# ST-LINK_V2-1_Klinovitskiy_Kirill.net
KiCad netlist of a schematic drawn in Altium Designer
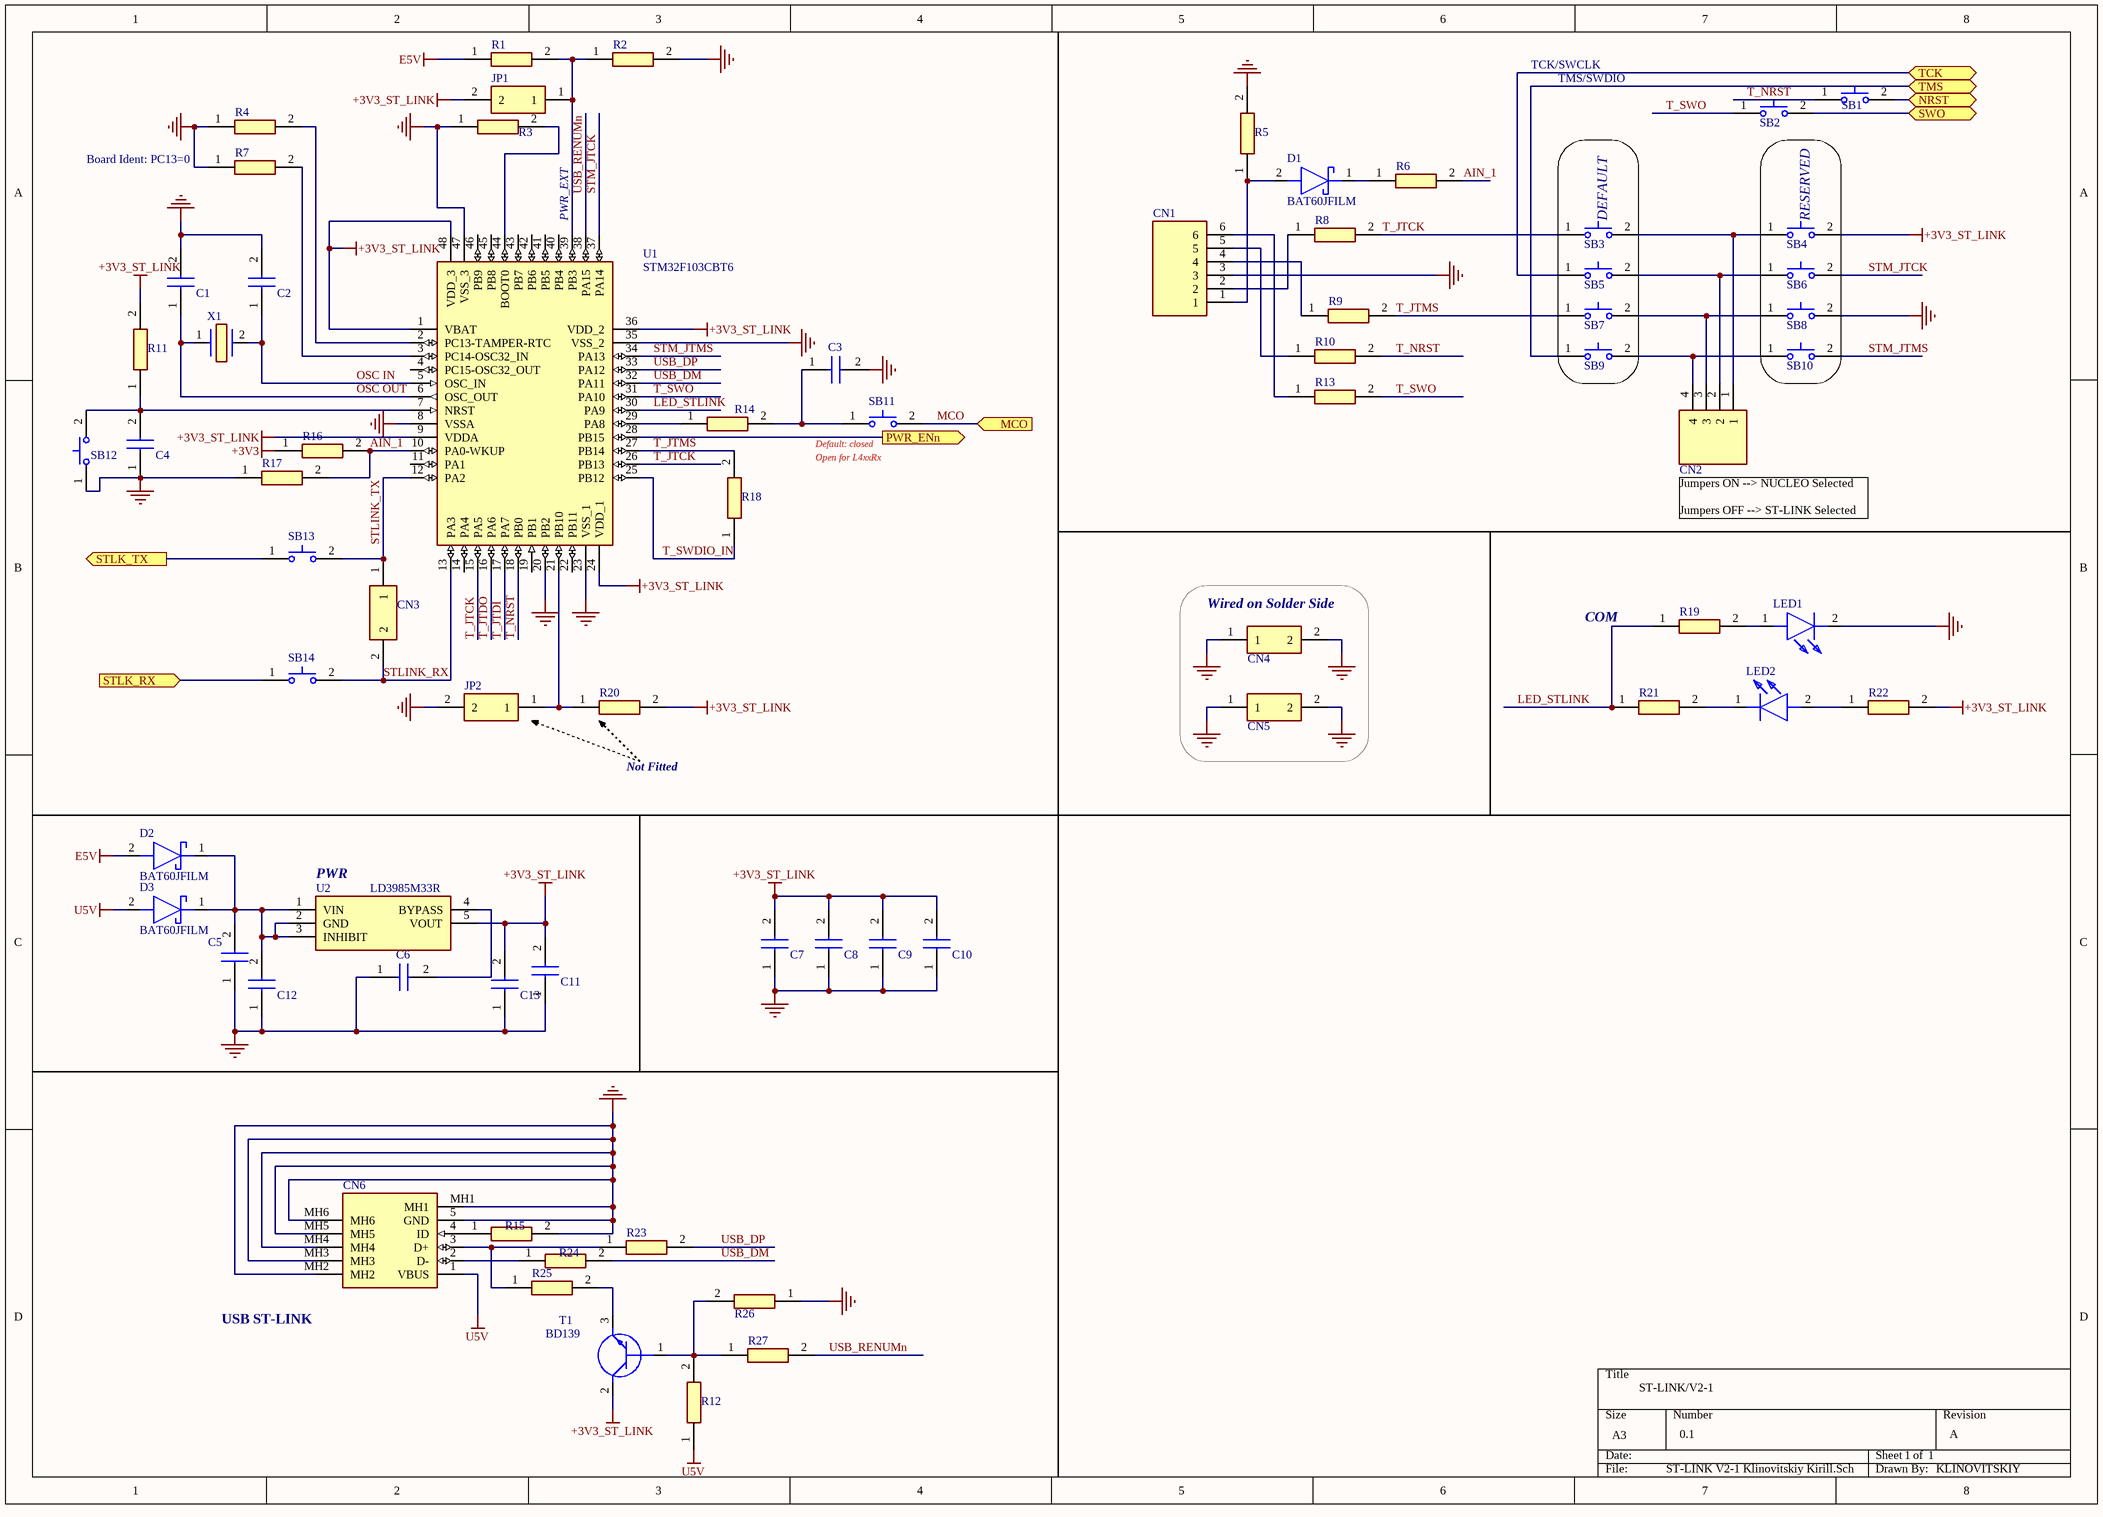
[diagram p0: ST-LINK V2-1 Klinovitskiy Kirill.SchDoc]

(export (version "E")
  (design (tool "Eeschema 10.0.6"))
  (components
    (comp (ref "C1")
      (value "C1206C200KCGACTU")
      (footprint "SamacSys:C1206")
      (description "Capacitor")
      (libsource (lib "*") (part "C1206C200KCGACTU"))
    )
    (comp (ref "C2")
      (value "C1206C200KCGACTU")
      (footprint "SamacSys:C1206")
      (description "Capacitor")
      (libsource (lib "*") (part "C1206C200KCGACTU"))
    )
    (comp (ref "C3")
      (value "C1206C200KCGACTU")
      (footprint "SamacSys:C1206")
      (description "Capacitor")
      (libsource (lib "*") (part "C1206C200KCGACTU"))
    )
    (comp (ref "C4")
      (value "06035C104K4T4A")
      (footprint "SamacSys:CAPC1608X90N")
      (description "Capacitor")
      (fields (field (name "MOUSER PART NUMBER") "581-06035C104K4T4A"))
      (libsource (lib "*") (part "06035C104K4T4A"))
    )
    (comp (ref "C5")
      (value "MAJCT168BB7105KTEA01")
      (footprint "SamacSys:MAJx16")
      (description "Capacitor")
      (libsource (lib "*") (part "MAJCT168BB7105KTEA01"))
    )
    (comp (ref "C6")
      (value "KGM31GCG2J103JU")
      (footprint "SamacSys:CAPC3316X145N")
      (description "Capacitor")
      (fields (field (name "MOUSER PART NUMBER") "581-KGM31GCG2J103JU"))
      (libsource (lib "*") (part "KGM31GCG2J103JU"))
    )
    (comp (ref "C7")
      (value "06035C104K4T4A")
      (footprint "SamacSys:CAPC1608X90N")
      (description "Capacitor")
      (fields (field (name "MOUSER PART NUMBER") "581-06035C104K4T4A"))
      (libsource (lib "*") (part "06035C104K4T4A"))
    )
    (comp (ref "C8")
      (value "06035C104K4T4A")
      (footprint "SamacSys:CAPC1608X90N")
      (description "Capacitor")
      (fields (field (name "MOUSER PART NUMBER") "581-06035C104K4T4A"))
      (libsource (lib "*") (part "06035C104K4T4A"))
    )
    (comp (ref "C9")
      (value "06035C104K4T4A")
      (footprint "SamacSys:CAPC1608X90N")
      (description "Capacitor")
      (fields (field (name "MOUSER PART NUMBER") "581-06035C104K4T4A"))
      (libsource (lib "*") (part "06035C104K4T4A"))
    )
    (comp (ref "C10")
      (value "06035C104K4T4A")
      (footprint "SamacSys:CAPC1608X90N")
      (description "Capacitor")
      (fields (field (name "MOUSER PART NUMBER") "581-06035C104K4T4A"))
      (libsource (lib "*") (part "06035C104K4T4A"))
    )
    (comp (ref "C11")
      (value "06035C104K4T4A")
      (footprint "SamacSys:CAPC1608X90N")
      (description "Capacitor")
      (fields (field (name "MOUSER PART NUMBER") "581-06035C104K4T4A"))
      (libsource (lib "*") (part "06035C104K4T4A"))
    )
    (comp (ref "C12")
      (value "06035C104K4T4A")
      (footprint "SamacSys:CAPC1608X90N")
      (description "Capacitor")
      (fields (field (name "MOUSER PART NUMBER") "581-06035C104K4T4A"))
      (libsource (lib "*") (part "06035C104K4T4A"))
    )
    (comp (ref "C13")
      (value "MAJCT168BB7105KTEA01")
      (footprint "SamacSys:MAJx16")
      (description "Capacitor")
      (libsource (lib "*") (part "MAJCT168BB7105KTEA01"))
    )
    (comp (ref "CN1")
      (value "22-28-4062")
      (footprint "SamacSys:HDRV6W66P0X254_1X6_1524X249X838P")
      (description "Connector")
      (fields (field (name "MOUSER PART NUMBER") "538-22-28-4062"))
      (libsource (lib "*") (part "22-28-4062"))
    )
    (comp (ref "CN2")
      (value "53014-0410")
      (footprint "SamacSys:SHDR4W60P0X200_1X4_1200X435X1000P")
      (description "Connector")
      (fields (field (name "MOUSER PART NUMBER") "538-53014-0410"))
      (libsource (lib "*") (part "53014-0410"))
    )
    (comp (ref "CN3")
      (value "3-647166-2")
      (footprint "SamacSys:36471662")
      (description "Connector")
      (fields (field (name "MOUSER PART NUMBER") "571-3-647166-2"))
      (libsource (lib "") (part "3-647166-2_2"))
    )
    (comp (ref "CN4")
      (value "3-647166-2")
      (footprint "SamacSys:36471662")
      (description "Connector")
      (fields (field (name "MOUSER PART NUMBER") "571-3-647166-2"))
      (libsource (lib "*") (part "3-647166-2"))
    )
    (comp (ref "CN5")
      (value "3-647166-2")
      (footprint "SamacSys:36471662")
      (description "Connector")
      (fields (field (name "MOUSER PART NUMBER") "571-3-647166-2"))
      (libsource (lib "*") (part "3-647166-2"))
    )
    (comp (ref "CN6")
      (value "204926-1103")
      (footprint "SamacSys:2049261103")
      (description "Connector")
      (fields (field (name "MOUSER PART NUMBER") "538-204926-1103"))
      (libsource (lib "*") (part "204926-1103"))
    )
    (comp (ref "D1")
      (value "BAT60JFILM")
      (footprint "SamacSys:SOD2513X117N")
      (description "Schottky Diode")
      (fields (field (name "MOUSER PART NUMBER") "511-BAT60JFILM"))
      (libsource (lib "*") (part "BAT60JFILM"))
    )
    (comp (ref "D2")
      (value "BAT60JFILM")
      (footprint "SamacSys:SOD2513X117N")
      (description "Schottky Diode")
      (fields (field (name "MOUSER PART NUMBER") "511-BAT60JFILM"))
      (libsource (lib "*") (part "BAT60JFILM"))
    )
    (comp (ref "D3")
      (value "BAT60JFILM")
      (footprint "SamacSys:SOD2513X117N")
      (description "Schottky Diode")
      (fields (field (name "MOUSER PART NUMBER") "511-BAT60JFILM"))
      (libsource (lib "*") (part "BAT60JFILM"))
    )
    (comp (ref "JP1")
      (value "3-647166-2")
      (footprint "SamacSys:36471662")
      (description "Connector")
      (fields (field (name "MOUSER PART NUMBER") "571-3-647166-2"))
      (libsource (lib "") (part "3-647166-2_1"))
    )
    (comp (ref "JP2")
      (value "3-647166-2")
      (footprint "SamacSys:36471662")
      (description "Connector")
      (fields (field (name "MOUSER PART NUMBER") "571-3-647166-2"))
      (libsource (lib "") (part "3-647166-2_1"))
    )
    (comp (ref "LED1")
      (value "C4SMA-RGY-CS4V1BB1")
      (footprint "SamacSys:C4SMARGYCS4V1BB1")
      (description "LED")
      (fields (field (name "MOUSER PART NUMBER") "941-C4SMARGYCS4V1BB1"))
      (libsource (lib "*") (part "C4SMA-RGY-CS4V1BB1"))
    )
    (comp (ref "LED2")
      (value "TLHG5420-ASZ")
      (footprint "SamacSys:TLHG5420ASZ")
      (description "LED")
      (fields (field (name "MOUSER PART NUMBER") "78-TLHG5420-ASZ"))
      (libsource (lib "*") (part "TLHG5420-ASZ"))
    )
    (comp (ref "R1")
      (value "CRCW12102K70FKEAHP")
      (footprint "SamacSys:RESC3225X70N")
      (description "Resistor")
      (fields (field (name "MOUSER PART NUMBER") "71-CRCW12102K70FKEAH"))
      (libsource (lib "*") (part "CRCW12102K70FKEAHP"))
    )
    (comp (ref "R2")
      (value "MCS04020D4701BE000")
      (footprint "SamacSys:RESC1005X37N")
      (description "Resistor")
      (fields (field (name "MOUSER PART NUMBER") "594-MCS04020D4701BE0"))
      (libsource (lib "*") (part "MCS04020D4701BE000"))
    )
    (comp (ref "R3")
      (value "SFR01MZPF1003")
      (footprint "SamacSys:RESC1005X40N")
      (description "Resistor")
      (fields (field (name "MOUSER PART NUMBER") "755-SFR01MZPF1003"))
      (libsource (lib "") (part "SFR01MZPF1003_1"))
    )
    (comp (ref "R4")
      (value "CRM2512QJW-103ELF")
      (footprint "SamacSys:RESC6331X80N")
      (description "Resistor")
      (fields (field (name "MOUSER PART NUMBER") "652-CRM2512QJW-103E"))
      (libsource (lib "*") (part "CRM2512QJW-103ELF"))
    )
    (comp (ref "R5")
      (value "CRM2512QJW-103ELF")
      (footprint "SamacSys:RESC6331X80N")
      (description "Resistor")
      (fields (field (name "MOUSER PART NUMBER") "652-CRM2512QJW-103E"))
      (libsource (lib "") (part "CRM2512QJW-103ELF_1"))
    )
    (comp (ref "R6")
      (value "ERA-3AED101V")
      (footprint "SamacSys:ERA3AEB101V")
      (description "Resistor")
      (fields (field (name "MOUSER PART NUMBER") "667-ERA-3AED101V"))
      (libsource (lib "*") (part "ERA-3AED101V"))
    )
    (comp (ref "R7")
      (value "CRM2512QJW-103ELF")
      (footprint "SamacSys:RESC6331X80N")
      (description "Resistor")
      (fields (field (name "MOUSER PART NUMBER") "652-CRM2512QJW-103E"))
      (libsource (lib "*") (part "CRM2512QJW-103ELF"))
    )
    (comp (ref "R8")
      (value "ERA-6AHD220V")
      (footprint "SamacSys:ERA6AEB1020V")
      (description "Resistor")
      (fields (field (name "MOUSER PART NUMBER") "667-ERA-6AHD220V"))
      (libsource (lib "*") (part "ERA-6AHD220V"))
    )
    (comp (ref "R9")
      (value "ERA-6AHD220V")
      (footprint "SamacSys:ERA6AEB1020V")
      (description "Resistor")
      (fields (field (name "MOUSER PART NUMBER") "667-ERA-6AHD220V"))
      (libsource (lib "*") (part "ERA-6AHD220V"))
    )
    (comp (ref "R10")
      (value "ERA-6AHD220V")
      (footprint "SamacSys:ERA6AEB1020V")
      (description "Resistor")
      (fields (field (name "MOUSER PART NUMBER") "667-ERA-6AHD220V"))
      (libsource (lib "*") (part "ERA-6AHD220V"))
    )
    (comp (ref "R11")
      (value "SFR01MZPF1003")
      (footprint "SamacSys:RESC1005X40N")
      (description "Resistor")
      (fields (field (name "MOUSER PART NUMBER") "755-SFR01MZPF1003"))
      (libsource (lib "*") (part "SFR01MZPF1003"))
    )
    (comp (ref "R12")
      (value "CRM2512QJW-103ELF")
      (footprint "SamacSys:RESC6331X80N")
      (description "Resistor")
      (fields (field (name "MOUSER PART NUMBER") "652-CRM2512QJW-103E"))
      (libsource (lib "") (part "CRM2512QJW-103ELF_1"))
    )
    (comp (ref "R13")
      (value "ERA-6AHD220V")
      (footprint "SamacSys:ERA6AEB1020V")
      (description "Resistor")
      (fields (field (name "MOUSER PART NUMBER") "667-ERA-6AHD220V"))
      (libsource (lib "*") (part "ERA-6AHD220V"))
    )
    (comp (ref "R14")
      (value "ERA-3AED101V")
      (footprint "SamacSys:ERA3AEB101V")
      (description "Resistor")
      (fields (field (name "MOUSER PART NUMBER") "667-ERA-3AED101V"))
      (libsource (lib "*") (part "ERA-3AED101V"))
    )
    (comp (ref "R15")
      (value "SFR01MZPF1003")
      (footprint "SamacSys:RESC1005X40N")
      (description "Resistor")
      (fields (field (name "MOUSER PART NUMBER") "755-SFR01MZPF1003"))
      (libsource (lib "") (part "SFR01MZPF1003_1"))
    )
    (comp (ref "R16")
      (value "MCS04020D4701BE000")
      (footprint "SamacSys:RESC1005X37N")
      (description "Resistor")
      (fields (field (name "MOUSER PART NUMBER") "594-MCS04020D4701BE0"))
      (libsource (lib "*") (part "MCS04020D4701BE000"))
    )
    (comp (ref "R17")
      (value "MCS04020D4701BE000")
      (footprint "SamacSys:RESC1005X37N")
      (description "Resistor")
      (fields (field (name "MOUSER PART NUMBER") "594-MCS04020D4701BE0"))
      (libsource (lib "*") (part "MCS04020D4701BE000"))
    )
    (comp (ref "R18")
      (value "ERA-3AED101V")
      (footprint "SamacSys:ERA3AEB101V")
      (description "Resistor")
      (fields (field (name "MOUSER PART NUMBER") "667-ERA-3AED101V"))
      (libsource (lib "") (part "ERA-3AED101V_1"))
    )
    (comp (ref "R19")
      (value "ERA-3AED101V")
      (footprint "SamacSys:ERA3AEB101V")
      (description "Resistor")
      (fields (field (name "MOUSER PART NUMBER") "667-ERA-3AED101V"))
      (libsource (lib "*") (part "ERA-3AED101V"))
    )
    (comp (ref "R20")
      (value "WSL080500000ZEA9")
      (footprint "SamacSys:RESC2013X84N")
      (description "Resistor")
      (fields (field (name "MOUSER PART NUMBER") "71-WSL080500000ZEA9"))
      (libsource (lib "*") (part "WSL080500000ZEA9"))
    )
    (comp (ref "R21")
      (value "ERA-3AED101V")
      (footprint "SamacSys:ERA3AEB101V")
      (description "Resistor")
      (fields (field (name "MOUSER PART NUMBER") "667-ERA-3AED101V"))
      (libsource (lib "*") (part "ERA-3AED101V"))
    )
    (comp (ref "R22")
      (value "WSL080500000ZEA9")
      (footprint "SamacSys:RESC2013X84N")
      (description "Resistor")
      (fields (field (name "MOUSER PART NUMBER") "71-WSL080500000ZEA9"))
      (libsource (lib "*") (part "WSL080500000ZEA9"))
    )
    (comp (ref "R23")
      (value "WSL080500000ZEA9")
      (footprint "SamacSys:RESC2013X84N")
      (description "Resistor")
      (fields (field (name "MOUSER PART NUMBER") "71-WSL080500000ZEA9"))
      (libsource (lib "*") (part "WSL080500000ZEA9"))
    )
    (comp (ref "R24")
      (value "WSL080500000ZEA9")
      (footprint "SamacSys:RESC2013X84N")
      (description "Resistor")
      (fields (field (name "MOUSER PART NUMBER") "71-WSL080500000ZEA9"))
      (libsource (lib "*") (part "WSL080500000ZEA9"))
    )
    (comp (ref "R25")
      (value "CRCW12061K50FKEAHP")
      (footprint "SamacSys:RESC3116X65N")
      (description "Resistor")
      (fields (field (name "MOUSER PART NUMBER") "71-CRCW12061K50FKEAH"))
      (libsource (lib "*") (part "CRCW12061K50FKEAHP"))
    )
    (comp (ref "R26")
      (value "TNPW080536K0BEEA")
      (footprint "SamacSys:RESC2012X55N")
      (description "Resistor")
      (libsource (lib "*") (part "TNPW080536K0BEEA"))
    )
    (comp (ref "R27")
      (value "ERA-3AED101V")
      (footprint "SamacSys:ERA3AEB101V")
      (description "Resistor")
      (fields (field (name "MOUSER PART NUMBER") "667-ERA-3AED101V"))
      (libsource (lib "*") (part "ERA-3AED101V"))
    )
    (comp (ref "SB1")
      (value "8631CQD2")
      (footprint "SamacSys:8631CQD2")
      (description "Switch (2-Pin Push)")
      (fields (field (name "MOUSER PART NUMBER") "611-8631-261"))
      (libsource (lib "*") (part "8631CQD2"))
    )
    (comp (ref "SB2")
      (value "8631CQD2")
      (footprint "SamacSys:8631CQD2")
      (description "Switch (2-Pin Push)")
      (fields (field (name "MOUSER PART NUMBER") "611-8631-261"))
      (libsource (lib "*") (part "8631CQD2"))
    )
    (comp (ref "SB3")
      (value "8631CQD2")
      (footprint "SamacSys:8631CQD2")
      (description "Switch (2-Pin Push)")
      (fields (field (name "MOUSER PART NUMBER") "611-8631-261"))
      (libsource (lib "*") (part "8631CQD2"))
    )
    (comp (ref "SB4")
      (value "8631CQD2")
      (footprint "SamacSys:8631CQD2")
      (description "Switch (2-Pin Push)")
      (fields (field (name "MOUSER PART NUMBER") "611-8631-261"))
      (libsource (lib "*") (part "8631CQD2"))
    )
    (comp (ref "SB5")
      (value "8631CQD2")
      (footprint "SamacSys:8631CQD2")
      (description "Switch (2-Pin Push)")
      (fields (field (name "MOUSER PART NUMBER") "611-8631-261"))
      (libsource (lib "*") (part "8631CQD2"))
    )
    (comp (ref "SB6")
      (value "8631CQD2")
      (footprint "SamacSys:8631CQD2")
      (description "Switch (2-Pin Push)")
      (fields (field (name "MOUSER PART NUMBER") "611-8631-261"))
      (libsource (lib "*") (part "8631CQD2"))
    )
    (comp (ref "SB7")
      (value "8631CQD2")
      (footprint "SamacSys:8631CQD2")
      (description "Switch (2-Pin Push)")
      (fields (field (name "MOUSER PART NUMBER") "611-8631-261"))
      (libsource (lib "*") (part "8631CQD2"))
    )
    (comp (ref "SB8")
      (value "8631CQD2")
      (footprint "SamacSys:8631CQD2")
      (description "Switch (2-Pin Push)")
      (fields (field (name "MOUSER PART NUMBER") "611-8631-261"))
      (libsource (lib "*") (part "8631CQD2"))
    )
    (comp (ref "SB9")
      (value "8631CQD2")
      (footprint "SamacSys:8631CQD2")
      (description "Switch (2-Pin Push)")
      (fields (field (name "MOUSER PART NUMBER") "611-8631-261"))
      (libsource (lib "*") (part "8631CQD2"))
    )
    (comp (ref "SB10")
      (value "8631CQD2")
      (footprint "SamacSys:8631CQD2")
      (description "Switch (2-Pin Push)")
      (fields (field (name "MOUSER PART NUMBER") "611-8631-261"))
      (libsource (lib "*") (part "8631CQD2"))
    )
    (comp (ref "SB11")
      (value "8631CQD2")
      (footprint "SamacSys:8631CQD2")
      (description "Switch (2-Pin Push)")
      (fields (field (name "MOUSER PART NUMBER") "611-8631-261"))
      (libsource (lib "*") (part "8631CQD2"))
    )
    (comp (ref "SB12")
      (value "8631CQD2")
      (footprint "SamacSys:8631CQD2")
      (description "Switch (2-Pin Push)")
      (fields (field (name "MOUSER PART NUMBER") "611-8631-261"))
      (libsource (lib "*") (part "8631CQD2"))
    )
    (comp (ref "SB13")
      (value "8631CQD2")
      (footprint "SamacSys:8631CQD2")
      (description "Switch (2-Pin Push)")
      (fields (field (name "MOUSER PART NUMBER") "611-8631-261"))
      (libsource (lib "*") (part "8631CQD2"))
    )
    (comp (ref "SB14")
      (value "8631CQD2")
      (footprint "SamacSys:8631CQD2")
      (description "Switch (2-Pin Push)")
      (fields (field (name "MOUSER PART NUMBER") "611-8631-261"))
      (libsource (lib "*") (part "8631CQD2"))
    )
    (comp (ref "T1")
      (value "BD139")
      (footprint "SamacSys:TO254P290X760X1320-3P")
      (description "Transistor BJT NPN")
      (fields (field (name "MOUSER PART NUMBER") "511-BD139"))
      (libsource (lib "*") (part "BD139"))
    )
    (comp (ref "U1")
      (value "STM32F103CBT6")
      (footprint "SamacSys:QFP50P900X900X160-48N")
      (description "Integrated Circuit")
      (fields (field (name "MOUSER PART NUMBER") "511-STM32F103CBT6"))
      (libsource (lib "*") (part "STM32F103CBT6"))
    )
    (comp (ref "U2")
      (value "LD3985M33R")
      (footprint "SamacSys:SOT95P280X145-5N")
      (description "Integrated Circuit")
      (fields (field (name "MOUSER PART NUMBER") "511-LD3985M33R"))
      (libsource (lib "*") (part "LD3985M33R"))
    )
    (comp (ref "X1")
      (value "ECS-80-12-5PX-GM-TR")
      (footprint "SamacSys:ECS80125PXGMTR")
      (description "Crystal or Oscillator")
      (fields (field (name "MOUSER PART NUMBER") "520-80-12-5PX-GM-TR"))
      (libsource (lib "*") (part "ECS-80-12-5PX-GM-TR"))
    )
  )
  (nets
    (net (code "1") (name "+3V3") (class "Default")
      (node (ref "R16") (pin "1") (pinfunction "1_1") (pintype "passive"))
    )
    (net (code "2") (name "+3V3_ST_LINK") (class "Default")
      (node (ref "C10") (pin "2") (pinfunction "2_2") (pintype "passive"))
      (node (ref "C11") (pin "2") (pinfunction "2_2") (pintype "passive"))
      (node (ref "C13") (pin "2") (pinfunction "2_2") (pintype "passive"))
      (node (ref "C7") (pin "2") (pinfunction "2_2") (pintype "passive"))
      (node (ref "C8") (pin "2") (pinfunction "2_2") (pintype "passive"))
      (node (ref "C9") (pin "2") (pinfunction "2_2") (pintype "passive"))
      (node (ref "JP1") (pin "2") (pinfunction "2_2") (pintype "passive"))
      (node (ref "R11") (pin "2") (pinfunction "2_2") (pintype "passive"))
      (node (ref "R20") (pin "2") (pinfunction "2_2") (pintype "passive"))
      (node (ref "R22") (pin "2") (pinfunction "2_2") (pintype "passive"))
      (node (ref "SB4") (pin "2") (pinfunction "N.O._2_2") (pintype "passive"))
      (node (ref "T1") (pin "2") (pinfunction "C_2") (pintype "passive"))
      (node (ref "U1") (pin "1") (pinfunction "VBAT_1") (pintype "passive"))
      (node (ref "U1") (pin "24") (pinfunction "VDD_1_24") (pintype "passive"))
      (node (ref "U1") (pin "36") (pinfunction "VDD_2_36") (pintype "passive"))
      (node (ref "U1") (pin "48") (pinfunction "VDD_3_48") (pintype "passive"))
      (node (ref "U1") (pin "9") (pinfunction "VDDA_9") (pintype "passive"))
      (node (ref "U2") (pin "5") (pinfunction "VOUT_5") (pintype "passive"))
    )
    (net (code "3") (name "/AIN_1") (class "Default")
      (node (ref "R16") (pin "2") (pinfunction "2_2") (pintype "passive"))
      (node (ref "R17") (pin "2") (pinfunction "2_2") (pintype "passive"))
      (node (ref "R6") (pin "2") (pinfunction "2_2") (pintype "passive"))
      (node (ref "U1") (pin "10") (pinfunction "PA0-WKUP_10") (pintype "bidirectional"))
    )
    (net (code "4") (name "/LED_STLINK") (class "Default")
      (node (ref "R19") (pin "1") (pinfunction "1_1") (pintype "passive"))
      (node (ref "R21") (pin "1") (pinfunction "1_1") (pintype "passive"))
      (node (ref "U1") (pin "30") (pinfunction "PA9_30") (pintype "bidirectional"))
    )
    (net (code "5") (name "/MCO") (class "Default")
      (node (ref "SB11") (pin "2") (pinfunction "N.O._2_2") (pintype "passive"))
    )
    (net (code "6") (name "/NRST") (class "Default")
      (node (ref "SB1") (pin "2") (pinfunction "N.O._2_2") (pintype "passive"))
    )
    (net (code "7") (name "/OSC IN") (class "Default")
      (node (ref "C2") (pin "1") (pinfunction "1_1") (pintype "passive"))
      (node (ref "U1") (pin "5") (pinfunction "OSC_IN_5") (pintype "input"))
      (node (ref "X1") (pin "2") (pinfunction "2_2") (pintype "passive"))
    )
    (net (code "8") (name "/OSC OUT") (class "Default")
      (node (ref "C1") (pin "1") (pinfunction "1_1") (pintype "passive"))
      (node (ref "U1") (pin "6") (pinfunction "OSC_OUT_6") (pintype "output"))
      (node (ref "X1") (pin "1") (pinfunction "1_1") (pintype "passive"))
    )
    (net (code "9") (name "/PWR_ENn") (class "Default")
      (node (ref "U1") (pin "28") (pinfunction "PB15_28") (pintype "bidirectional"))
    )
    (net (code "10") (name "/STLINK_RX") (class "Default")
      (node (ref "CN3") (pin "2") (pinfunction "2_2") (pintype "passive"))
      (node (ref "SB14") (pin "2") (pinfunction "N.O._2_2") (pintype "passive"))
      (node (ref "U1") (pin "13") (pinfunction "PA3_13") (pintype "bidirectional"))
    )
    (net (code "11") (name "/STLINK_TX") (class "Default")
      (node (ref "CN3") (pin "1") (pinfunction "1_1") (pintype "passive"))
      (node (ref "SB13") (pin "2") (pinfunction "N.O._2_2") (pintype "passive"))
      (node (ref "U1") (pin "12") (pinfunction "PA2_12") (pintype "bidirectional"))
    )
    (net (code "12") (name "/STLK_RX") (class "Default")
      (node (ref "SB14") (pin "1") (pinfunction "N.O._1_1") (pintype "passive"))
    )
    (net (code "13") (name "/STLK_TX") (class "Default")
      (node (ref "SB13") (pin "1") (pinfunction "N.O._1_1") (pintype "passive"))
    )
    (net (code "14") (name "/STM_JTCK") (class "Default")
      (node (ref "SB6") (pin "2") (pinfunction "N.O._2_2") (pintype "passive"))
      (node (ref "U1") (pin "37") (pinfunction "PA14_37") (pintype "bidirectional"))
    )
    (net (code "15") (name "/STM_JTMS") (class "Default")
      (node (ref "SB10") (pin "2") (pinfunction "N.O._2_2") (pintype "passive"))
      (node (ref "U1") (pin "34") (pinfunction "PA13_34") (pintype "bidirectional"))
    )
    (net (code "16") (name "/SWO") (class "Default")
      (node (ref "SB2") (pin "2") (pinfunction "N.O._2_2") (pintype "passive"))
    )
    (net (code "17") (name "/TCK") (class "Default")
      (node (ref "SB5") (pin "1") (pinfunction "N.O._1_1") (pintype "passive"))
    )
    (net (code "18") (name "/TMS") (class "Default")
      (node (ref "SB9") (pin "1") (pinfunction "N.O._1_1") (pintype "passive"))
    )
    (net (code "19") (name "/T_JTCK") (class "Default")
      (node (ref "R8") (pin "2") (pinfunction "2_2") (pintype "passive"))
      (node (ref "SB3") (pin "1") (pinfunction "N.O._1_1") (pintype "passive"))
      (node (ref "U1") (pin "15") (pinfunction "PA5_15") (pintype "bidirectional"))
      (node (ref "U1") (pin "26") (pinfunction "PB13_26") (pintype "bidirectional"))
    )
    (net (code "20") (name "/T_JTDI") (class "Default")
      (node (ref "U1") (pin "17") (pinfunction "PA7_17") (pintype "bidirectional"))
    )
    (net (code "21") (name "/T_JTDO") (class "Default")
      (node (ref "U1") (pin "16") (pinfunction "PA6_16") (pintype "bidirectional"))
    )
    (net (code "22") (name "/T_JTMS") (class "Default")
      (node (ref "R18") (pin "2") (pinfunction "2_2") (pintype "passive"))
      (node (ref "R9") (pin "2") (pinfunction "2_2") (pintype "passive"))
      (node (ref "SB7") (pin "1") (pinfunction "N.O._1_1") (pintype "passive"))
      (node (ref "U1") (pin "27") (pinfunction "PB14_27") (pintype "bidirectional"))
    )
    (net (code "23") (name "/T_NRST") (class "Default")
      (node (ref "R10") (pin "2") (pinfunction "2_2") (pintype "passive"))
      (node (ref "SB1") (pin "1") (pinfunction "N.O._1_1") (pintype "passive"))
      (node (ref "U1") (pin "18") (pinfunction "PB0_18") (pintype "bidirectional"))
    )
    (net (code "24") (name "/T_SWDIO_IN") (class "Default")
      (node (ref "R18") (pin "1") (pinfunction "1_1") (pintype "passive"))
      (node (ref "U1") (pin "25") (pinfunction "PB12_25") (pintype "bidirectional"))
    )
    (net (code "25") (name "/T_SWO") (class "Default")
      (node (ref "R13") (pin "2") (pinfunction "2_2") (pintype "passive"))
      (node (ref "SB2") (pin "1") (pinfunction "N.O._1_1") (pintype "passive"))
      (node (ref "U1") (pin "31") (pinfunction "PA10_31") (pintype "bidirectional"))
    )
    (net (code "26") (name "/USB_DM") (class "Default")
      (node (ref "R24") (pin "2") (pinfunction "2_2") (pintype "passive"))
      (node (ref "U1") (pin "32") (pinfunction "PA11_32") (pintype "bidirectional"))
    )
    (net (code "27") (name "/USB_DP") (class "Default")
      (node (ref "R23") (pin "2") (pinfunction "2_2") (pintype "passive"))
      (node (ref "U1") (pin "33") (pinfunction "PA12_33") (pintype "bidirectional"))
    )
    (net (code "28") (name "/USB_RENUMn") (class "Default")
      (node (ref "R27") (pin "2") (pinfunction "2_2") (pintype "passive"))
      (node (ref "U1") (pin "38") (pinfunction "PA15_38") (pintype "bidirectional"))
    )
    (net (code "29") (name "E5V") (class "Default")
      (node (ref "D2") (pin "2") (pinfunction "A_2") (pintype "passive"))
      (node (ref "R1") (pin "1") (pinfunction "1_1") (pintype "passive"))
    )
    (net (code "30") (name "GND") (class "Default")
      (node (ref "C1") (pin "2") (pinfunction "2_2") (pintype "passive"))
      (node (ref "C10") (pin "1") (pinfunction "1_1") (pintype "passive"))
      (node (ref "C11") (pin "1") (pinfunction "1_1") (pintype "passive"))
      (node (ref "C12") (pin "1") (pinfunction "1_1") (pintype "passive"))
      (node (ref "C13") (pin "1") (pinfunction "1_1") (pintype "passive"))
      (node (ref "C2") (pin "2") (pinfunction "2_2") (pintype "passive"))
      (node (ref "C3") (pin "2") (pinfunction "2_2") (pintype "passive"))
      (node (ref "C4") (pin "1") (pinfunction "1_1") (pintype "passive"))
      (node (ref "C5") (pin "1") (pinfunction "1_1") (pintype "passive"))
      (node (ref "C6") (pin "1") (pinfunction "1_1") (pintype "passive"))
      (node (ref "C7") (pin "1") (pinfunction "1_1") (pintype "passive"))
      (node (ref "C8") (pin "1") (pinfunction "1_1") (pintype "passive"))
      (node (ref "C9") (pin "1") (pinfunction "1_1") (pintype "passive"))
      (node (ref "CN1") (pin "3") (pinfunction "3_3") (pintype "passive"))
      (node (ref "CN4") (pin "1") (pinfunction "1_1") (pintype "passive"))
      (node (ref "CN4") (pin "2") (pinfunction "2_2") (pintype "passive"))
      (node (ref "CN5") (pin "1") (pinfunction "1_1") (pintype "passive"))
      (node (ref "CN5") (pin "2") (pinfunction "2_2") (pintype "passive"))
      (node (ref "CN6") (pin "5") (pinfunction "GND_5") (pintype "passive"))
      (node (ref "CN6") (pin "MH1") (pinfunction "MH1_MH1") (pintype "passive"))
      (node (ref "CN6") (pin "MH2") (pinfunction "MH2_MH2") (pintype "passive"))
      (node (ref "CN6") (pin "MH3") (pinfunction "MH3_MH3") (pintype "passive"))
      (node (ref "CN6") (pin "MH4") (pinfunction "MH4_MH4") (pintype "passive"))
      (node (ref "CN6") (pin "MH5") (pinfunction "MH5_MH5") (pintype "passive"))
      (node (ref "CN6") (pin "MH6") (pinfunction "MH6_MH6") (pintype "passive"))
      (node (ref "JP2") (pin "2") (pinfunction "2_2") (pintype "passive"))
      (node (ref "LED1") (pin "2") (pinfunction "K_2") (pintype "passive"))
      (node (ref "R15") (pin "2") (pinfunction "2_2") (pintype "passive"))
      (node (ref "R17") (pin "1") (pinfunction "1_1") (pintype "passive"))
      (node (ref "R2") (pin "2") (pinfunction "2_2") (pintype "passive"))
      (node (ref "R26") (pin "1") (pinfunction "1_1") (pintype "passive"))
      (node (ref "R3") (pin "1") (pinfunction "1_1") (pintype "passive"))
      (node (ref "R4") (pin "1") (pinfunction "1_1") (pintype "passive"))
      (node (ref "R5") (pin "2") (pinfunction "2_2") (pintype "passive"))
      (node (ref "R7") (pin "1") (pinfunction "1_1") (pintype "passive"))
      (node (ref "SB12") (pin "1") (pinfunction "N.O._1_1") (pintype "passive"))
      (node (ref "SB8") (pin "2") (pinfunction "N.O._2_2") (pintype "passive"))
      (node (ref "U1") (pin "20") (pinfunction "PB2_20") (pintype "bidirectional"))
      (node (ref "U1") (pin "23") (pinfunction "VSS_1_23") (pintype "passive"))
      (node (ref "U1") (pin "35") (pinfunction "VSS_2_35") (pintype "passive"))
      (node (ref "U1") (pin "47") (pinfunction "VSS_3_47") (pintype "passive"))
      (node (ref "U1") (pin "8") (pinfunction "VSSA_8") (pintype "passive"))
    )
    (net (code "31") (name "Net-(CN1-Pad2)") (class "Default")
      (node (ref "CN1") (pin "2") (pinfunction "2_2") (pintype "passive"))
      (node (ref "R8") (pin "1") (pinfunction "1_1") (pintype "passive"))
    )
    (net (code "32") (name "Net-(CN1-Pad4)") (class "Default")
      (node (ref "CN1") (pin "4") (pinfunction "4_4") (pintype "passive"))
      (node (ref "R9") (pin "1") (pinfunction "1_1") (pintype "passive"))
    )
    (net (code "33") (name "Net-(CN1-Pad5)") (class "Default")
      (node (ref "CN1") (pin "5") (pinfunction "5_5") (pintype "passive"))
      (node (ref "R10") (pin "1") (pinfunction "1_1") (pintype "passive"))
    )
    (net (code "34") (name "Net-(CN1-Pad6)") (class "Default")
      (node (ref "CN1") (pin "6") (pinfunction "6_6") (pintype "passive"))
      (node (ref "R13") (pin "1") (pinfunction "1_1") (pintype "passive"))
    )
    (net (code "35") (name "Net-(CN6-D+)") (class "Default")
      (node (ref "CN6") (pin "3") (pinfunction "D+_3") (pintype "bidirectional"))
      (node (ref "R23") (pin "1") (pinfunction "1_1") (pintype "passive"))
      (node (ref "R25") (pin "1") (pinfunction "1_1") (pintype "passive"))
    )
    (net (code "36") (name "Net-(CN6-D-)") (class "Default")
      (node (ref "CN6") (pin "2") (pinfunction "D-_2") (pintype "bidirectional"))
      (node (ref "R24") (pin "1") (pinfunction "1_1") (pintype "passive"))
    )
    (net (code "37") (name "Net-(CN6-ID)") (class "Default")
      (node (ref "CN6") (pin "4") (pinfunction "ID_4") (pintype "input"))
      (node (ref "R15") (pin "1") (pinfunction "1_1") (pintype "passive"))
    )
    (net (code "38") (name "Net-(D1-A)") (class "Default")
      (node (ref "CN1") (pin "1") (pinfunction "1_1") (pintype "passive"))
      (node (ref "D1") (pin "2") (pinfunction "A_2") (pintype "passive"))
      (node (ref "R5") (pin "1") (pinfunction "1_1") (pintype "passive"))
    )
    (net (code "39") (name "Net-(D1-K)") (class "Default")
      (node (ref "D1") (pin "1") (pinfunction "K_1") (pintype "passive"))
      (node (ref "R6") (pin "1") (pinfunction "1_1") (pintype "passive"))
    )
    (net (code "40") (name "Net-(D2-K)") (class "Default")
      (node (ref "C12") (pin "2") (pinfunction "2_2") (pintype "passive"))
      (node (ref "C5") (pin "2") (pinfunction "2_2") (pintype "passive"))
      (node (ref "D2") (pin "1") (pinfunction "K_1") (pintype "passive"))
      (node (ref "D3") (pin "1") (pinfunction "K_1") (pintype "passive"))
      (node (ref "U2") (pin "1") (pinfunction "VIN_1") (pintype "passive"))
      (node (ref "U2") (pin "2") (pinfunction "GND_2") (pintype "passive"))
      (node (ref "U2") (pin "3") (pinfunction "INHIBIT_3") (pintype "passive"))
    )
    (net (code "41") (name "Net-(LED1-A)") (class "Default")
      (node (ref "LED1") (pin "1") (pinfunction "A_1") (pintype "passive"))
      (node (ref "R19") (pin "2") (pinfunction "2_2") (pintype "passive"))
    )
    (net (code "42") (name "Net-(LED2-A)") (class "Default")
      (node (ref "LED2") (pin "2") (pinfunction "A_2") (pintype "passive"))
      (node (ref "R22") (pin "1") (pinfunction "1_1") (pintype "passive"))
    )
    (net (code "43") (name "Net-(LED2-K)") (class "Default")
      (node (ref "LED2") (pin "1") (pinfunction "K_1") (pintype "passive"))
      (node (ref "R21") (pin "2") (pinfunction "2_2") (pintype "passive"))
    )
    (net (code "44") (name "Net-(SB3-N.O._2)") (class "Default")
      (node (ref "CN2") (pin "1") (pinfunction "1_1") (pintype "passive"))
      (node (ref "SB3") (pin "2") (pinfunction "N.O._2_2") (pintype "passive"))
      (node (ref "SB4") (pin "1") (pinfunction "N.O._1_1") (pintype "passive"))
    )
    (net (code "45") (name "Net-(SB5-N.O._2)") (class "Default")
      (node (ref "CN2") (pin "2") (pinfunction "2_2") (pintype "passive"))
      (node (ref "SB5") (pin "2") (pinfunction "N.O._2_2") (pintype "passive"))
      (node (ref "SB6") (pin "1") (pinfunction "N.O._1_1") (pintype "passive"))
    )
    (net (code "46") (name "Net-(SB7-N.O._2)") (class "Default")
      (node (ref "CN2") (pin "3") (pinfunction "3_3") (pintype "passive"))
      (node (ref "SB7") (pin "2") (pinfunction "N.O._2_2") (pintype "passive"))
      (node (ref "SB8") (pin "1") (pinfunction "N.O._1_1") (pintype "passive"))
    )
    (net (code "47") (name "Net-(SB10-N.O._1)") (class "Default")
      (node (ref "CN2") (pin "4") (pinfunction "4_4") (pintype "passive"))
      (node (ref "SB10") (pin "1") (pinfunction "N.O._1_1") (pintype "passive"))
      (node (ref "SB9") (pin "2") (pinfunction "N.O._2_2") (pintype "passive"))
    )
    (net (code "48") (name "Net-(SB11-N.O._1)") (class "Default")
      (node (ref "C3") (pin "1") (pinfunction "1_1") (pintype "passive"))
      (node (ref "R14") (pin "2") (pinfunction "2_2") (pintype "passive"))
      (node (ref "SB11") (pin "1") (pinfunction "N.O._1_1") (pintype "passive"))
    )
    (net (code "49") (name "Net-(SB12-N.O._2)") (class "Default")
      (node (ref "C4") (pin "2") (pinfunction "2_2") (pintype "passive"))
      (node (ref "R11") (pin "1") (pinfunction "1_1") (pintype "passive"))
      (node (ref "SB12") (pin "2") (pinfunction "N.O._2_2") (pintype "passive"))
      (node (ref "U1") (pin "7") (pinfunction "NRST_7") (pintype "input"))
    )
    (net (code "50") (name "Net-(T1-B)") (class "Default")
      (node (ref "R12") (pin "2") (pinfunction "2_2") (pintype "passive"))
      (node (ref "R26") (pin "2") (pinfunction "2_2") (pintype "passive"))
      (node (ref "R27") (pin "1") (pinfunction "1_1") (pintype "passive"))
      (node (ref "T1") (pin "1") (pinfunction "B_1") (pintype "passive"))
    )
    (net (code "51") (name "Net-(T1-E)") (class "Default")
      (node (ref "R25") (pin "2") (pinfunction "2_2") (pintype "passive"))
      (node (ref "T1") (pin "3") (pinfunction "E_3") (pintype "passive"))
    )
    (net (code "52") (name "Net-(U1-BOOT0)") (class "Default")
      (node (ref "R3") (pin "2") (pinfunction "2_2") (pintype "passive"))
      (node (ref "U1") (pin "44") (pinfunction "BOOT0_44") (pintype "bidirectional"))
    )
    (net (code "53") (name "Net-(U1-PA8)") (class "Default")
      (node (ref "R14") (pin "1") (pinfunction "1_1") (pintype "passive"))
      (node (ref "U1") (pin "29") (pinfunction "PA8_29") (pintype "bidirectional"))
    )
    (net (code "54") (name "Net-(U1-PB3)") (class "Default")
      (node (ref "JP1") (pin "1") (pinfunction "1_1") (pintype "passive"))
      (node (ref "R1") (pin "2") (pinfunction "2_2") (pintype "passive"))
      (node (ref "R2") (pin "1") (pinfunction "1_1") (pintype "passive"))
      (node (ref "U1") (pin "39") (pinfunction "PB3_39") (pintype "bidirectional"))
    )
    (net (code "55") (name "Net-(U1-PB10)") (class "Default")
      (node (ref "JP2") (pin "1") (pinfunction "1_1") (pintype "passive"))
      (node (ref "R20") (pin "1") (pinfunction "1_1") (pintype "passive"))
      (node (ref "U1") (pin "21") (pinfunction "PB10_21") (pintype "bidirectional"))
    )
    (net (code "56") (name "Net-(U1-PC13-TAMPER-RTC)") (class "Default")
      (node (ref "R4") (pin "2") (pinfunction "2_2") (pintype "passive"))
      (node (ref "U1") (pin "2") (pinfunction "PC13-TAMPER-RTC_2") (pintype "bidirectional"))
    )
    (net (code "57") (name "Net-(U1-PC14-OSC32_IN)") (class "Default")
      (node (ref "R7") (pin "2") (pinfunction "2_2") (pintype "passive"))
      (node (ref "U1") (pin "3") (pinfunction "PC14-OSC32_IN_3") (pintype "bidirectional"))
    )
    (net (code "58") (name "Net-(U2-BYPASS)") (class "Default")
      (node (ref "C6") (pin "2") (pinfunction "2_2") (pintype "passive"))
      (node (ref "U2") (pin "4") (pinfunction "BYPASS_4") (pintype "passive"))
    )
    (net (code "59") (name "U5V") (class "Default")
      (node (ref "CN6") (pin "1") (pinfunction "VBUS_1") (pintype "passive"))
      (node (ref "D3") (pin "2") (pinfunction "A_2") (pintype "passive"))
      (node (ref "R12") (pin "1") (pinfunction "1_1") (pintype "passive"))
    )
    (net (code "60") (name "unconnected-(U1-PA1-Pad11)") (class "Default")
      (node (ref "U1") (pin "11") (pinfunction "PA1_11") (pintype "bidirectional"))
    )
    (net (code "61") (name "unconnected-(U1-PA4-Pad14)") (class "Default")
      (node (ref "U1") (pin "14") (pinfunction "PA4_14") (pintype "bidirectional"))
    )
    (net (code "62") (name "unconnected-(U1-PB1-Pad19)") (class "Default")
      (node (ref "U1") (pin "19") (pinfunction "PB1_19") (pintype "input"))
    )
    (net (code "63") (name "unconnected-(U1-PB4-Pad40)") (class "Default")
      (node (ref "U1") (pin "40") (pinfunction "PB4_40") (pintype "bidirectional"))
    )
    (net (code "64") (name "unconnected-(U1-PB5-Pad41)") (class "Default")
      (node (ref "U1") (pin "41") (pinfunction "PB5_41") (pintype "bidirectional"))
    )
    (net (code "65") (name "unconnected-(U1-PB6-Pad42)") (class "Default")
      (node (ref "U1") (pin "42") (pinfunction "PB6_42") (pintype "bidirectional"))
    )
    (net (code "66") (name "unconnected-(U1-PB7-Pad43)") (class "Default")
      (node (ref "U1") (pin "43") (pinfunction "PB7_43") (pintype "bidirectional"))
    )
    (net (code "67") (name "unconnected-(U1-PB8-Pad45)") (class "Default")
      (node (ref "U1") (pin "45") (pinfunction "PB8_45") (pintype "bidirectional"))
    )
    (net (code "68") (name "unconnected-(U1-PB9-Pad46)") (class "Default")
      (node (ref "U1") (pin "46") (pinfunction "PB9_46") (pintype "bidirectional"))
    )
    (net (code "69") (name "unconnected-(U1-PB11-Pad22)") (class "Default")
      (node (ref "U1") (pin "22") (pinfunction "PB11_22") (pintype "bidirectional"))
    )
    (net (code "70") (name "unconnected-(U1-PC15-OSC32_OUT-Pad4)") (class "Default")
      (node (ref "U1") (pin "4") (pinfunction "PC15-OSC32_OUT_4") (pintype "bidirectional"))
    )
  )
)
